# DigiGlove_conn_board.net
KiCad netlist of a schematic drawn in EAGLE
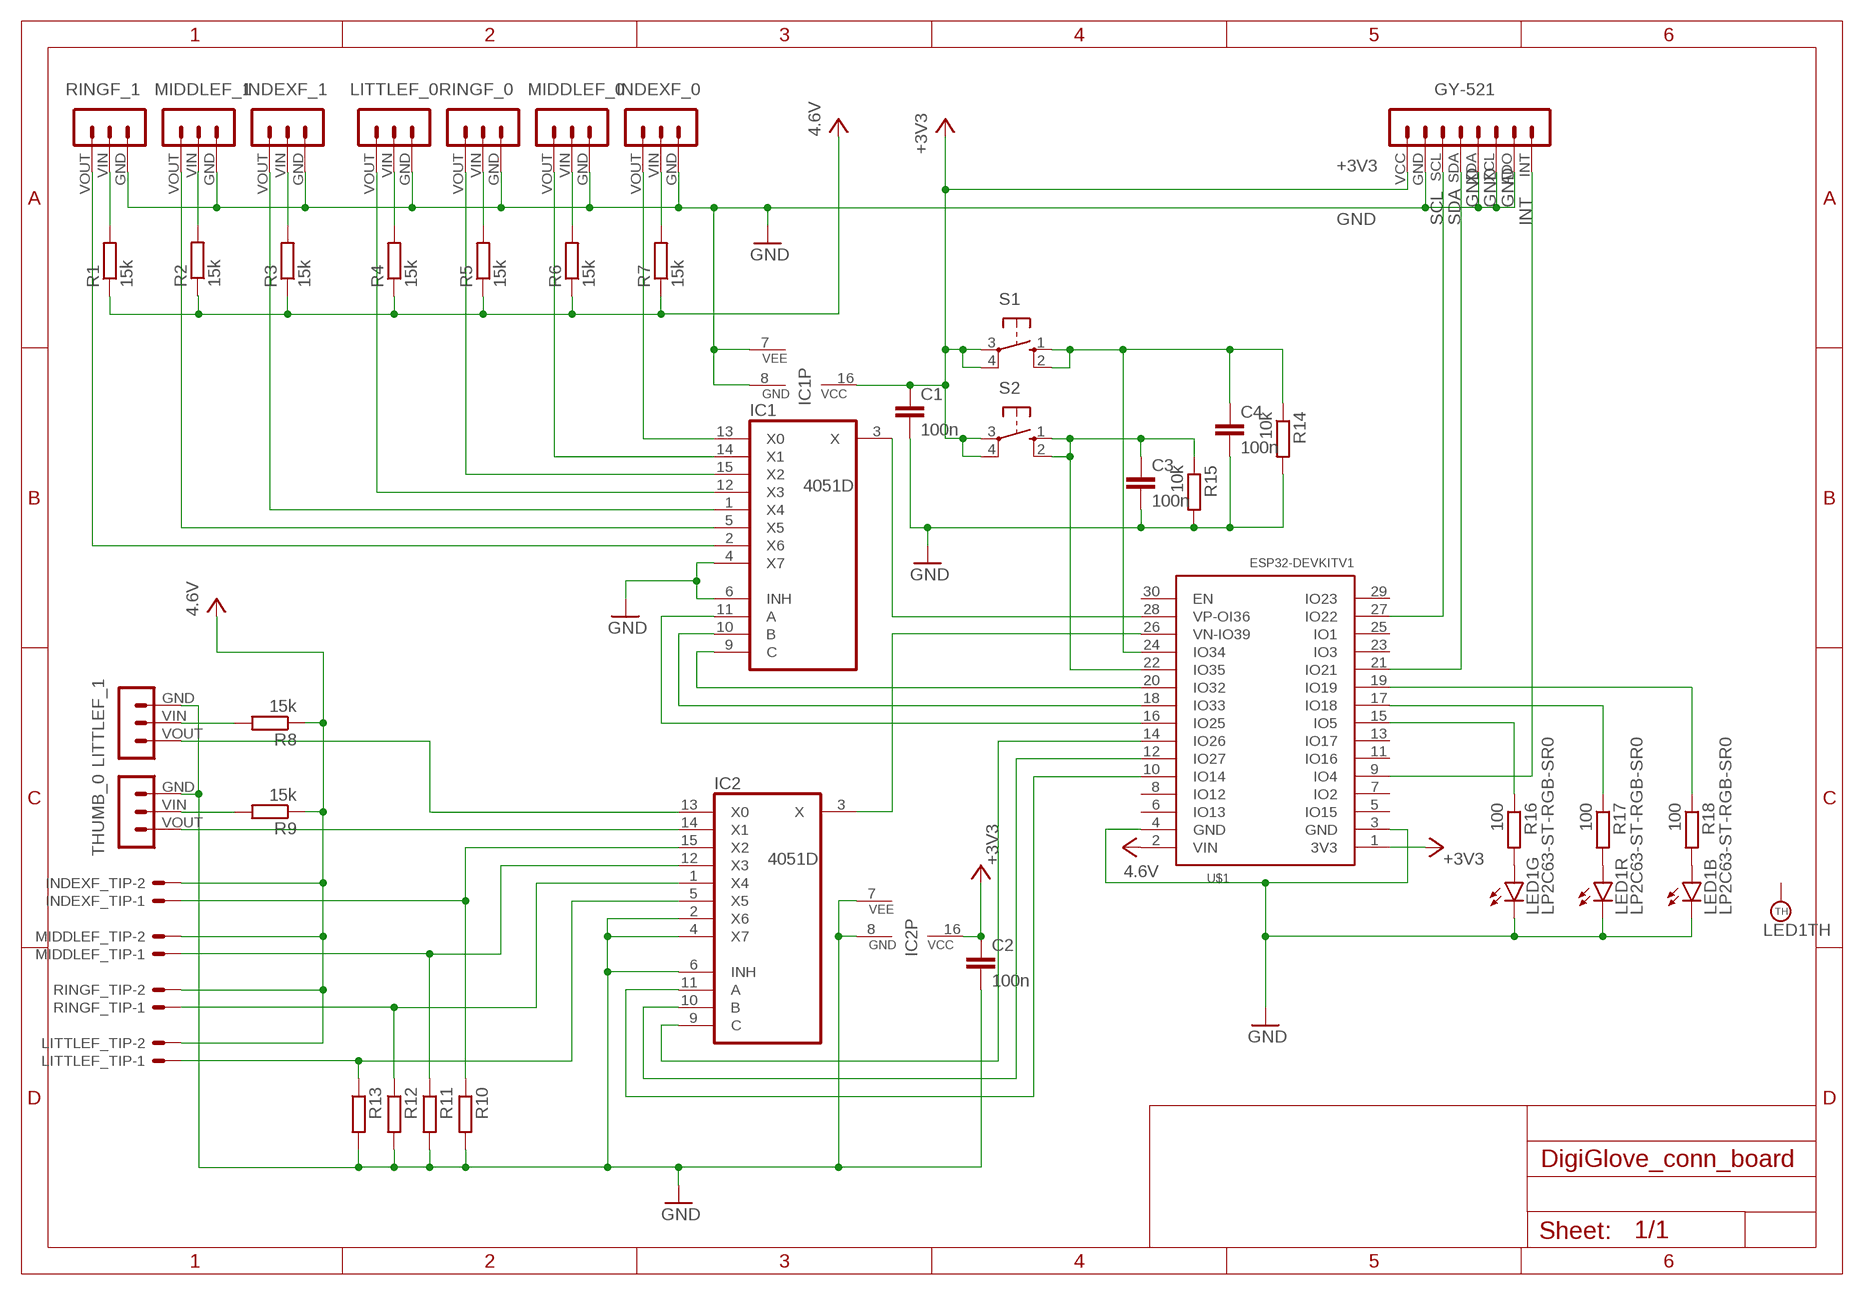
[diagram p0: schematic, sheet 1]

(export (version "E")
  (design (tool "Eeschema 10.0.6"))
  (components
    (comp (ref "C1")
      (value "100n")
      (footprint "eagle-import:C1608")
      (libsource (lib "eagle-import") (part "C-EUC1608"))
    )
    (comp (ref "C2")
      (value "100n")
      (footprint "eagle-import:C1608")
      (libsource (lib "eagle-import") (part "C-EUC1608"))
    )
    (comp (ref "C3")
      (value "100n")
      (footprint "eagle-import:C1608")
      (libsource (lib "eagle-import") (part "C-EUC1608"))
    )
    (comp (ref "C4")
      (value "100n")
      (footprint "eagle-import:C1608")
      (libsource (lib "eagle-import") (part "C-EUC1608"))
    )
    (comp (ref "GY-521")
      (value "MA08-1MA08-1_254")
      (footprint "eagle-import:PAD8_254")
      (libsource (lib "eagle-import") (part "MA08-1MA08-1_254"))
    )
    (comp (ref "IC1")
      (value "4051D")
      (footprint "eagle-import:SO16")
      (libsource (lib "eagle-import") (part "4051D"))
    )
    (comp (ref "IC2")
      (value "4051D")
      (footprint "eagle-import:SO16")
      (libsource (lib "eagle-import") (part "4051D"))
    )
    (comp (ref "INDEXF_0")
      (value "MA03-1MA03-1-254")
      (footprint "eagle-import:PAD3_254")
      (libsource (lib "eagle-import") (part "MA03-1MA03-1-254"))
    )
    (comp (ref "INDEXF_1")
      (value "MA03-1MA03-1-254")
      (footprint "eagle-import:PAD3_254")
      (libsource (lib "eagle-import") (part "MA03-1MA03-1-254"))
    )
    (comp (ref "INDEXF_TIP")
      (value "22-23-20212PIN_254")
      (footprint "eagle-import:PAD2_254")
      (libsource (lib "eagle-import") (part "22-23-20212PIN_254"))
    )
    (comp (ref "LED1")
      (value "LP2C63-ST-RGB-SR0")
      (footprint "eagle-import:LP2C63-ST-RGB-SR0")
      (libsource (lib "eagle-import") (part "LP2C63-ST-RGB-SR0"))
    )
    (comp (ref "LITTLEF_0")
      (value "MA03-1MA03-1-254")
      (footprint "eagle-import:PAD3_254")
      (libsource (lib "eagle-import") (part "MA03-1MA03-1-254"))
    )
    (comp (ref "LITTLEF_1")
      (value "MA03-1MA03-1-254")
      (footprint "eagle-import:PAD3_254")
      (libsource (lib "eagle-import") (part "MA03-1MA03-1-254"))
    )
    (comp (ref "LITTLEF_TIP")
      (value "22-23-20212PIN_254")
      (footprint "eagle-import:PAD2_254")
      (libsource (lib "eagle-import") (part "22-23-20212PIN_254"))
    )
    (comp (ref "MIDDLEF_0")
      (value "MA03-1MA03-1-254")
      (footprint "eagle-import:PAD3_254")
      (libsource (lib "eagle-import") (part "MA03-1MA03-1-254"))
    )
    (comp (ref "MIDDLEF_1")
      (value "MA03-1MA03-1-254")
      (footprint "eagle-import:PAD3_254")
      (libsource (lib "eagle-import") (part "MA03-1MA03-1-254"))
    )
    (comp (ref "MIDDLEF_TIP")
      (value "22-23-20212PIN_254")
      (footprint "eagle-import:PAD2_254")
      (libsource (lib "eagle-import") (part "22-23-20212PIN_254"))
    )
    (comp (ref "R1")
      (value "15k")
      (footprint "eagle-import:R2012")
      (libsource (lib "eagle-import") (part "R-EU_R2012"))
    )
    (comp (ref "R2")
      (value "15k")
      (footprint "eagle-import:R2012")
      (libsource (lib "eagle-import") (part "R-EU_R2012"))
    )
    (comp (ref "R3")
      (value "15k")
      (footprint "eagle-import:R2012")
      (libsource (lib "eagle-import") (part "R-EU_R2012"))
    )
    (comp (ref "R4")
      (value "15k")
      (footprint "eagle-import:R2012")
      (libsource (lib "eagle-import") (part "R-EU_R2012"))
    )
    (comp (ref "R5")
      (value "15k")
      (footprint "eagle-import:R2012")
      (libsource (lib "eagle-import") (part "R-EU_R2012"))
    )
    (comp (ref "R6")
      (value "15k")
      (footprint "eagle-import:R2012")
      (libsource (lib "eagle-import") (part "R-EU_R2012"))
    )
    (comp (ref "R7")
      (value "15k")
      (footprint "eagle-import:R2012")
      (libsource (lib "eagle-import") (part "R-EU_R2012"))
    )
    (comp (ref "R8")
      (value "15k")
      (footprint "eagle-import:R2012")
      (libsource (lib "eagle-import") (part "R-EU_R2012"))
    )
    (comp (ref "R9")
      (value "15k")
      (footprint "eagle-import:R2012")
      (libsource (lib "eagle-import") (part "R-EU_R2012"))
    )
    (comp (ref "R10")
      (value "R-EU_R2012")
      (footprint "eagle-import:R2012")
      (libsource (lib "eagle-import") (part "R-EU_R2012"))
    )
    (comp (ref "R11")
      (value "R-EU_R2012")
      (footprint "eagle-import:R2012")
      (libsource (lib "eagle-import") (part "R-EU_R2012"))
    )
    (comp (ref "R12")
      (value "R-EU_R2012")
      (footprint "eagle-import:R2012")
      (libsource (lib "eagle-import") (part "R-EU_R2012"))
    )
    (comp (ref "R13")
      (value "R-EU_R2012")
      (footprint "eagle-import:R2012")
      (libsource (lib "eagle-import") (part "R-EU_R2012"))
    )
    (comp (ref "R14")
      (value "10k")
      (footprint "eagle-import:R2012")
      (libsource (lib "eagle-import") (part "R-EU_R2012"))
    )
    (comp (ref "R15")
      (value "10k")
      (footprint "eagle-import:R2012")
      (libsource (lib "eagle-import") (part "R-EU_R2012"))
    )
    (comp (ref "R16")
      (value "100")
      (footprint "eagle-import:R0603")
      (libsource (lib "eagle-import") (part "R-EU_R0603"))
    )
    (comp (ref "R17")
      (value "100")
      (footprint "eagle-import:R0603")
      (libsource (lib "eagle-import") (part "R-EU_R0603"))
    )
    (comp (ref "R18")
      (value "100")
      (footprint "eagle-import:R0603")
      (libsource (lib "eagle-import") (part "R-EU_R0603"))
    )
    (comp (ref "RINGF_0")
      (value "MA03-1MA03-1-254")
      (footprint "eagle-import:PAD3_254")
      (libsource (lib "eagle-import") (part "MA03-1MA03-1-254"))
    )
    (comp (ref "RINGF_1")
      (value "MA03-1MA03-1-254")
      (footprint "eagle-import:PAD3_254")
      (libsource (lib "eagle-import") (part "MA03-1MA03-1-254"))
    )
    (comp (ref "RINGF_TIP")
      (value "22-23-20212PIN_254")
      (footprint "eagle-import:PAD2_254")
      (libsource (lib "eagle-import") (part "22-23-20212PIN_254"))
    )
    (comp (ref "S1")
      (value "10-XX")
      (footprint "eagle-import:B3F-10XX")
      (fields (field (name "MPN") "B3F-1000"))
      (libsource (lib "eagle-import") (part "10-XX"))
    )
    (comp (ref "S2")
      (value "10-XX")
      (footprint "eagle-import:B3F-10XX")
      (fields (field (name "MPN") "B3F-1000"))
      (libsource (lib "eagle-import") (part "10-XX"))
    )
    (comp (ref "THUMB_0")
      (value "MA03-1MA03-1-254")
      (footprint "eagle-import:PAD3_254")
      (libsource (lib "eagle-import") (part "MA03-1MA03-1-254"))
    )
    (comp (ref "U$1")
      (value "ESP32DEVKITV1HEADER")
      (footprint "eagle-import:MA17-2")
      (libsource (lib "eagle-import") (part "ESP32DEVKITV1HEADER"))
    )
  )
  (nets
    (net (code "1") (name "+3V3") (class "Default")
      (node (ref "C1") (pin "1") (pinfunction "1_1") (pintype "passive"))
      (node (ref "C2") (pin "1") (pinfunction "1_1") (pintype "passive"))
      (node (ref "GY-521") (pin "VCC") (pinfunction "VCC_VCC") (pintype "passive"))
      (node (ref "IC1") (pin "16") (pinfunction "VCC_16") (pintype "power_in"))
      (node (ref "IC2") (pin "16") (pinfunction "VCC_16") (pintype "power_in"))
      (node (ref "S1") (pin "3") (pinfunction "P_3") (pintype "passive"))
      (node (ref "S1") (pin "4") (pinfunction "P1_4") (pintype "passive"))
      (node (ref "S2") (pin "3") (pinfunction "P_3") (pintype "passive"))
      (node (ref "S2") (pin "4") (pinfunction "P1_4") (pintype "passive"))
      (node (ref "U$1") (pin "1") (pinfunction "3V3_1") (pintype "bidirectional"))
    )
    (net (code "2") (name "/INT") (class "Default")
      (node (ref "GY-521") (pin "INT") (pinfunction "INT_INT") (pintype "passive"))
      (node (ref "U$1") (pin "9") (pinfunction "IO4_9") (pintype "bidirectional"))
    )
    (net (code "3") (name "/SCL") (class "Default")
      (node (ref "GY-521") (pin "SCL") (pinfunction "SCL_SCL") (pintype "passive"))
      (node (ref "U$1") (pin "27") (pinfunction "IO22_27") (pintype "bidirectional"))
    )
    (net (code "4") (name "/SDA") (class "Default")
      (node (ref "GY-521") (pin "SDA") (pinfunction "SDA_SDA") (pintype "passive"))
      (node (ref "U$1") (pin "21") (pinfunction "IO21_21") (pintype "bidirectional"))
    )
    (net (code "5") (name "4.6V") (class "Default")
      (node (ref "INDEXF_TIP") (pin "P$2") (pinfunction "S_P$2") (pintype "passive"))
      (node (ref "LITTLEF_TIP") (pin "P$2") (pinfunction "S_P$2") (pintype "passive"))
      (node (ref "MIDDLEF_TIP") (pin "P$2") (pinfunction "S_P$2") (pintype "passive"))
      (node (ref "R1") (pin "1") (pinfunction "1_1") (pintype "passive"))
      (node (ref "R2") (pin "1") (pinfunction "1_1") (pintype "passive"))
      (node (ref "R3") (pin "1") (pinfunction "1_1") (pintype "passive"))
      (node (ref "R4") (pin "1") (pinfunction "1_1") (pintype "passive"))
      (node (ref "R5") (pin "1") (pinfunction "1_1") (pintype "passive"))
      (node (ref "R6") (pin "1") (pinfunction "1_1") (pintype "passive"))
      (node (ref "R7") (pin "1") (pinfunction "1_1") (pintype "passive"))
      (node (ref "R8") (pin "1") (pinfunction "1_1") (pintype "passive"))
      (node (ref "R9") (pin "1") (pinfunction "1_1") (pintype "passive"))
      (node (ref "RINGF_TIP") (pin "P$2") (pinfunction "S_P$2") (pintype "passive"))
      (node (ref "U$1") (pin "2") (pinfunction "VIN_2") (pintype "bidirectional"))
    )
    (net (code "6") (name "GND") (class "Default")
      (node (ref "C1") (pin "2") (pinfunction "2_2") (pintype "passive"))
      (node (ref "C2") (pin "2") (pinfunction "2_2") (pintype "passive"))
      (node (ref "C3") (pin "2") (pinfunction "2_2") (pintype "passive"))
      (node (ref "C4") (pin "2") (pinfunction "2_2") (pintype "passive"))
      (node (ref "GY-521") (pin "ADO") (pinfunction "ADO_ADO") (pintype "passive"))
      (node (ref "GY-521") (pin "GND") (pinfunction "GND_GND") (pintype "passive"))
      (node (ref "GY-521") (pin "XCL") (pinfunction "XCL_XCL") (pintype "passive"))
      (node (ref "GY-521") (pin "XDA") (pinfunction "XDA_XDA") (pintype "passive"))
      (node (ref "IC1") (pin "4") (pinfunction "X7_4") (pintype "bidirectional"))
      (node (ref "IC1") (pin "6") (pinfunction "INH_6") (pintype "input"))
      (node (ref "IC1") (pin "7") (pinfunction "VEE_7") (pintype "power_in"))
      (node (ref "IC1") (pin "8") (pinfunction "GND_8") (pintype "power_in"))
      (node (ref "IC2") (pin "2") (pinfunction "X6_2") (pintype "bidirectional"))
      (node (ref "IC2") (pin "4") (pinfunction "X7_4") (pintype "bidirectional"))
      (node (ref "IC2") (pin "6") (pinfunction "INH_6") (pintype "input"))
      (node (ref "IC2") (pin "7") (pinfunction "VEE_7") (pintype "power_in"))
      (node (ref "IC2") (pin "8") (pinfunction "GND_8") (pintype "power_in"))
      (node (ref "INDEXF_0") (pin "GND") (pinfunction "GND_GND") (pintype "passive"))
      (node (ref "INDEXF_1") (pin "GND") (pinfunction "GND_GND") (pintype "passive"))
      (node (ref "LED1") (pin "4") (pinfunction "C_4") (pintype "passive"))
      (node (ref "LED1") (pin "5") (pinfunction "C_5") (pintype "passive"))
      (node (ref "LED1") (pin "6") (pinfunction "C_6") (pintype "passive"))
      (node (ref "LITTLEF_0") (pin "GND") (pinfunction "GND_GND") (pintype "passive"))
      (node (ref "LITTLEF_1") (pin "GND") (pinfunction "GND_GND") (pintype "passive"))
      (node (ref "MIDDLEF_0") (pin "GND") (pinfunction "GND_GND") (pintype "passive"))
      (node (ref "MIDDLEF_1") (pin "GND") (pinfunction "GND_GND") (pintype "passive"))
      (node (ref "R10") (pin "2") (pinfunction "2_2") (pintype "passive"))
      (node (ref "R11") (pin "2") (pinfunction "2_2") (pintype "passive"))
      (node (ref "R12") (pin "2") (pinfunction "2_2") (pintype "passive"))
      (node (ref "R13") (pin "2") (pinfunction "2_2") (pintype "passive"))
      (node (ref "R14") (pin "2") (pinfunction "2_2") (pintype "passive"))
      (node (ref "R15") (pin "2") (pinfunction "2_2") (pintype "passive"))
      (node (ref "RINGF_0") (pin "GND") (pinfunction "GND_GND") (pintype "passive"))
      (node (ref "RINGF_1") (pin "GND") (pinfunction "GND_GND") (pintype "passive"))
      (node (ref "THUMB_0") (pin "GND") (pinfunction "GND_GND") (pintype "passive"))
      (node (ref "U$1") (pin "3") (pinfunction "GND_3") (pintype "bidirectional"))
      (node (ref "U$1") (pin "4") (pinfunction "GND_4") (pintype "bidirectional"))
    )
    (net (code "7") (name "Net-(IC1A-A)") (class "Default")
      (node (ref "IC1") (pin "11") (pinfunction "A_11") (pintype "input"))
      (node (ref "U$1") (pin "16") (pinfunction "IO25_16") (pintype "bidirectional"))
    )
    (net (code "8") (name "Net-(IC1A-B)") (class "Default")
      (node (ref "IC1") (pin "10") (pinfunction "B_10") (pintype "input"))
      (node (ref "U$1") (pin "18") (pinfunction "IO33_18") (pintype "bidirectional"))
    )
    (net (code "9") (name "Net-(IC1A-C)") (class "Default")
      (node (ref "IC1") (pin "9") (pinfunction "C_9") (pintype "input"))
      (node (ref "U$1") (pin "20") (pinfunction "IO32_20") (pintype "bidirectional"))
    )
    (net (code "10") (name "Net-(IC1A-X)") (class "Default")
      (node (ref "IC1") (pin "3") (pinfunction "X_3") (pintype "bidirectional"))
      (node (ref "U$1") (pin "28") (pinfunction "VP-OI36_28") (pintype "bidirectional"))
    )
    (net (code "11") (name "Net-(IC1A-X0)") (class "Default")
      (node (ref "IC1") (pin "13") (pinfunction "X0_13") (pintype "bidirectional"))
      (node (ref "INDEXF_0") (pin "VOUT") (pinfunction "VOUT_VOUT") (pintype "passive"))
    )
    (net (code "12") (name "Net-(IC1A-X1)") (class "Default")
      (node (ref "IC1") (pin "14") (pinfunction "X1_14") (pintype "bidirectional"))
      (node (ref "MIDDLEF_0") (pin "VOUT") (pinfunction "VOUT_VOUT") (pintype "passive"))
    )
    (net (code "13") (name "Net-(IC1A-X2)") (class "Default")
      (node (ref "IC1") (pin "15") (pinfunction "X2_15") (pintype "bidirectional"))
      (node (ref "RINGF_0") (pin "VOUT") (pinfunction "VOUT_VOUT") (pintype "passive"))
    )
    (net (code "14") (name "Net-(IC1A-X3)") (class "Default")
      (node (ref "IC1") (pin "12") (pinfunction "X3_12") (pintype "bidirectional"))
      (node (ref "LITTLEF_0") (pin "VOUT") (pinfunction "VOUT_VOUT") (pintype "passive"))
    )
    (net (code "15") (name "Net-(IC1A-X4)") (class "Default")
      (node (ref "IC1") (pin "1") (pinfunction "X4_1") (pintype "bidirectional"))
      (node (ref "INDEXF_1") (pin "VOUT") (pinfunction "VOUT_VOUT") (pintype "passive"))
    )
    (net (code "16") (name "Net-(IC1A-X5)") (class "Default")
      (node (ref "IC1") (pin "5") (pinfunction "X5_5") (pintype "bidirectional"))
      (node (ref "MIDDLEF_1") (pin "VOUT") (pinfunction "VOUT_VOUT") (pintype "passive"))
    )
    (net (code "17") (name "Net-(IC1A-X6)") (class "Default")
      (node (ref "IC1") (pin "2") (pinfunction "X6_2") (pintype "bidirectional"))
      (node (ref "RINGF_1") (pin "VOUT") (pinfunction "VOUT_VOUT") (pintype "passive"))
    )
    (net (code "18") (name "Net-(IC2A-A)") (class "Default")
      (node (ref "IC2") (pin "11") (pinfunction "A_11") (pintype "input"))
      (node (ref "U$1") (pin "10") (pinfunction "IO14_10") (pintype "bidirectional"))
    )
    (net (code "19") (name "Net-(IC2A-B)") (class "Default")
      (node (ref "IC2") (pin "10") (pinfunction "B_10") (pintype "input"))
      (node (ref "U$1") (pin "12") (pinfunction "IO27_12") (pintype "bidirectional"))
    )
    (net (code "20") (name "Net-(IC2A-C)") (class "Default")
      (node (ref "IC2") (pin "9") (pinfunction "C_9") (pintype "input"))
      (node (ref "U$1") (pin "14") (pinfunction "IO26_14") (pintype "bidirectional"))
    )
    (net (code "21") (name "Net-(IC2A-X)") (class "Default")
      (node (ref "IC2") (pin "3") (pinfunction "X_3") (pintype "bidirectional"))
      (node (ref "U$1") (pin "26") (pinfunction "VN-IO39_26") (pintype "bidirectional"))
    )
    (net (code "22") (name "Net-(IC2A-X0)") (class "Default")
      (node (ref "IC2") (pin "13") (pinfunction "X0_13") (pintype "bidirectional"))
      (node (ref "LITTLEF_1") (pin "VOUT") (pinfunction "VOUT_VOUT") (pintype "passive"))
    )
    (net (code "23") (name "Net-(IC2A-X1)") (class "Default")
      (node (ref "IC2") (pin "14") (pinfunction "X1_14") (pintype "bidirectional"))
      (node (ref "THUMB_0") (pin "VOUT") (pinfunction "VOUT_VOUT") (pintype "passive"))
    )
    (net (code "24") (name "Net-(IC2A-X2)") (class "Default")
      (node (ref "IC2") (pin "15") (pinfunction "X2_15") (pintype "bidirectional"))
      (node (ref "INDEXF_TIP") (pin "P$1") (pinfunction "S_P$1") (pintype "passive"))
      (node (ref "R10") (pin "1") (pinfunction "1_1") (pintype "passive"))
    )
    (net (code "25") (name "Net-(IC2A-X3)") (class "Default")
      (node (ref "IC2") (pin "12") (pinfunction "X3_12") (pintype "bidirectional"))
      (node (ref "MIDDLEF_TIP") (pin "P$1") (pinfunction "S_P$1") (pintype "passive"))
      (node (ref "R11") (pin "1") (pinfunction "1_1") (pintype "passive"))
    )
    (net (code "26") (name "Net-(IC2A-X4)") (class "Default")
      (node (ref "IC2") (pin "1") (pinfunction "X4_1") (pintype "bidirectional"))
      (node (ref "R12") (pin "1") (pinfunction "1_1") (pintype "passive"))
      (node (ref "RINGF_TIP") (pin "P$1") (pinfunction "S_P$1") (pintype "passive"))
    )
    (net (code "27") (name "Net-(IC2A-X5)") (class "Default")
      (node (ref "IC2") (pin "5") (pinfunction "X5_5") (pintype "bidirectional"))
      (node (ref "LITTLEF_TIP") (pin "P$1") (pinfunction "S_P$1") (pintype "passive"))
      (node (ref "R13") (pin "1") (pinfunction "1_1") (pintype "passive"))
    )
    (net (code "28") (name "Net-(INDEXF_0-PadVIN)") (class "Default")
      (node (ref "INDEXF_0") (pin "VIN") (pinfunction "VIN_VIN") (pintype "passive"))
      (node (ref "R7") (pin "2") (pinfunction "2_2") (pintype "passive"))
    )
    (net (code "29") (name "Net-(INDEXF_1-PadVIN)") (class "Default")
      (node (ref "INDEXF_1") (pin "VIN") (pinfunction "VIN_VIN") (pintype "passive"))
      (node (ref "R3") (pin "2") (pinfunction "2_2") (pintype "passive"))
    )
    (net (code "30") (name "Net-(LED1A-A)") (class "Default")
      (node (ref "LED1") (pin "3") (pinfunction "A_3") (pintype "passive"))
      (node (ref "R18") (pin "2") (pinfunction "2_2") (pintype "passive"))
    )
    (net (code "31") (name "Net-(LED1B-A)") (class "Default")
      (node (ref "LED1") (pin "1") (pinfunction "A_1") (pintype "passive"))
      (node (ref "R16") (pin "2") (pinfunction "2_2") (pintype "passive"))
    )
    (net (code "32") (name "Net-(LED1C-A)") (class "Default")
      (node (ref "LED1") (pin "2") (pinfunction "A_2") (pintype "passive"))
      (node (ref "R17") (pin "2") (pinfunction "2_2") (pintype "passive"))
    )
    (net (code "33") (name "Net-(LITTLEF_0-PadVIN)") (class "Default")
      (node (ref "LITTLEF_0") (pin "VIN") (pinfunction "VIN_VIN") (pintype "passive"))
      (node (ref "R4") (pin "2") (pinfunction "2_2") (pintype "passive"))
    )
    (net (code "34") (name "Net-(LITTLEF_1-PadVIN)") (class "Default")
      (node (ref "LITTLEF_1") (pin "VIN") (pinfunction "VIN_VIN") (pintype "passive"))
      (node (ref "R8") (pin "2") (pinfunction "2_2") (pintype "passive"))
    )
    (net (code "35") (name "Net-(MIDDLEF_0-PadVIN)") (class "Default")
      (node (ref "MIDDLEF_0") (pin "VIN") (pinfunction "VIN_VIN") (pintype "passive"))
      (node (ref "R6") (pin "2") (pinfunction "2_2") (pintype "passive"))
    )
    (net (code "36") (name "Net-(MIDDLEF_1-PadVIN)") (class "Default")
      (node (ref "MIDDLEF_1") (pin "VIN") (pinfunction "VIN_VIN") (pintype "passive"))
      (node (ref "R2") (pin "2") (pinfunction "2_2") (pintype "passive"))
    )
    (net (code "37") (name "Net-(R1-Pad2)") (class "Default")
      (node (ref "R1") (pin "2") (pinfunction "2_2") (pintype "passive"))
      (node (ref "RINGF_1") (pin "VIN") (pinfunction "VIN_VIN") (pintype "passive"))
    )
    (net (code "38") (name "Net-(R5-Pad2)") (class "Default")
      (node (ref "R5") (pin "2") (pinfunction "2_2") (pintype "passive"))
      (node (ref "RINGF_0") (pin "VIN") (pinfunction "VIN_VIN") (pintype "passive"))
    )
    (net (code "39") (name "Net-(R9-Pad2)") (class "Default")
      (node (ref "R9") (pin "2") (pinfunction "2_2") (pintype "passive"))
      (node (ref "THUMB_0") (pin "VIN") (pinfunction "VIN_VIN") (pintype "passive"))
    )
    (net (code "40") (name "Net-(S1-S)") (class "Default")
      (node (ref "C4") (pin "1") (pinfunction "1_1") (pintype "passive"))
      (node (ref "R14") (pin "1") (pinfunction "1_1") (pintype "passive"))
      (node (ref "S1") (pin "1") (pinfunction "S_1") (pintype "passive"))
      (node (ref "S1") (pin "2") (pinfunction "S1_2") (pintype "passive"))
      (node (ref "U$1") (pin "24") (pinfunction "IO34_24") (pintype "bidirectional"))
    )
    (net (code "41") (name "Net-(S2-S)") (class "Default")
      (node (ref "C3") (pin "1") (pinfunction "1_1") (pintype "passive"))
      (node (ref "R15") (pin "1") (pinfunction "1_1") (pintype "passive"))
      (node (ref "S2") (pin "1") (pinfunction "S_1") (pintype "passive"))
      (node (ref "S2") (pin "2") (pinfunction "S1_2") (pintype "passive"))
      (node (ref "U$1") (pin "22") (pinfunction "IO35_22") (pintype "bidirectional"))
    )
    (net (code "42") (name "Net-(U$1-IO5)") (class "Default")
      (node (ref "R16") (pin "1") (pinfunction "1_1") (pintype "passive"))
      (node (ref "U$1") (pin "15") (pinfunction "IO5_15") (pintype "bidirectional"))
    )
    (net (code "43") (name "Net-(U$1-IO18)") (class "Default")
      (node (ref "R17") (pin "1") (pinfunction "1_1") (pintype "passive"))
      (node (ref "U$1") (pin "17") (pinfunction "IO18_17") (pintype "bidirectional"))
    )
    (net (code "44") (name "Net-(U$1-IO19)") (class "Default")
      (node (ref "R18") (pin "1") (pinfunction "1_1") (pintype "passive"))
      (node (ref "U$1") (pin "19") (pinfunction "IO19_19") (pintype "bidirectional"))
    )
    (net (code "45") (name "unconnected-(LED1-PadTH)") (class "Default")
      (node (ref "LED1") (pin "TH") (pinfunction "TH_TH") (pintype "passive"))
    )
    (net (code "46") (name "unconnected-(U$1-EN-Pad30)") (class "Default")
      (node (ref "U$1") (pin "30") (pinfunction "EN_30") (pintype "bidirectional"))
    )
    (net (code "47") (name "unconnected-(U$1-IO1-Pad25)") (class "Default")
      (node (ref "U$1") (pin "25") (pinfunction "IO1_25") (pintype "bidirectional"))
    )
    (net (code "48") (name "unconnected-(U$1-IO2-Pad7)") (class "Default")
      (node (ref "U$1") (pin "7") (pinfunction "IO2_7") (pintype "bidirectional"))
    )
    (net (code "49") (name "unconnected-(U$1-IO3-Pad23)") (class "Default")
      (node (ref "U$1") (pin "23") (pinfunction "IO3_23") (pintype "bidirectional"))
    )
    (net (code "50") (name "unconnected-(U$1-IO12-Pad8)") (class "Default")
      (node (ref "U$1") (pin "8") (pinfunction "IO12_8") (pintype "bidirectional"))
    )
    (net (code "51") (name "unconnected-(U$1-IO13-Pad6)") (class "Default")
      (node (ref "U$1") (pin "6") (pinfunction "IO13_6") (pintype "bidirectional"))
    )
    (net (code "52") (name "unconnected-(U$1-IO15-Pad5)") (class "Default")
      (node (ref "U$1") (pin "5") (pinfunction "IO15_5") (pintype "bidirectional"))
    )
    (net (code "53") (name "unconnected-(U$1-IO16-Pad11)") (class "Default")
      (node (ref "U$1") (pin "11") (pinfunction "IO16_11") (pintype "bidirectional"))
    )
    (net (code "54") (name "unconnected-(U$1-IO17-Pad13)") (class "Default")
      (node (ref "U$1") (pin "13") (pinfunction "IO17_13") (pintype "bidirectional"))
    )
    (net (code "55") (name "unconnected-(U$1-IO23-Pad29)") (class "Default")
      (node (ref "U$1") (pin "29") (pinfunction "IO23_29") (pintype "bidirectional"))
    )
  )
)
